# PowerManagement.net
KiCad netlist of a schematic drawn in Altium Designer
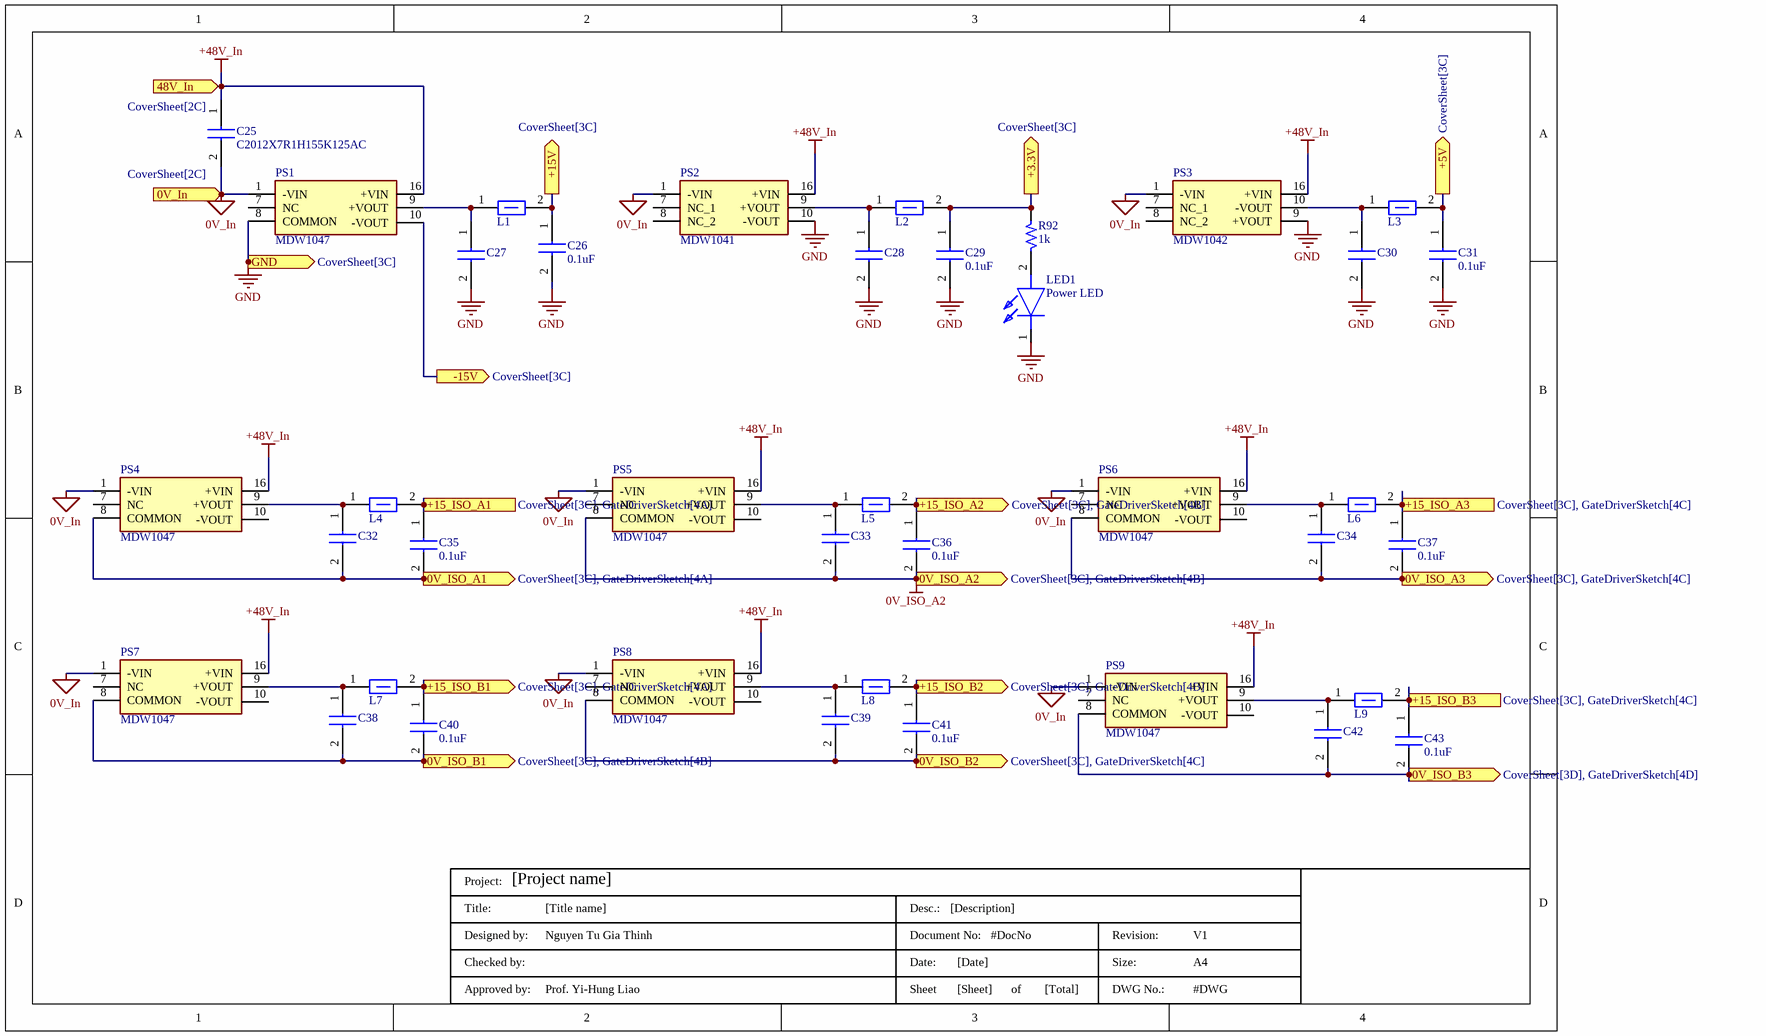
[diagram p0: PowerManagement.SchDoc]

(export (version "E")
  (design (tool "Eeschema 10.0.6"))
  (components
    (comp (ref "C25")
      (value "C2012X7R1H155K125AC")
      (footprint "SamacSys:CAPC2012X145N")
      (description "Capacitor")
      (fields (field (name "MOUSER PART NUMBER") "810-C2012X7R1H155K"))
      (libsource (lib "SamacSys") (part "C2012X7R1H155K125AC"))
    )
    (comp (ref "C26")
      (value "0.1uF")
      (footprint "SamacSys:C0805")
      (description "Capacitor")
      (fields
        (field (name "MANUFACTURER_PART_NUMBER") "C0805C104K3RACTU")
        (field (name "MOUSER PART NUMBER") "80-C0805C104K3R")
      )
      (libsource (lib "SamacSys") (part "C0805C104K3RACTU"))
    )
    (comp (ref "C27")
      (value "CGA4J1X7R1E335K125AC")
      (footprint "SamacSys:CAPC2012X145N")
      (description "Capacitor")
      (fields (field (name "MOUSER PART NUMBER") "810-CGA4J1X7R1E335K"))
      (libsource (lib "SamacSys") (part "CGA4J1X7R1E335K125AC"))
    )
    (comp (ref "C28")
      (value "CGA4J1X7R1E335K125AC")
      (footprint "SamacSys:CAPC2012X145N")
      (description "Capacitor")
      (fields (field (name "MOUSER PART NUMBER") "810-CGA4J1X7R1E335K"))
      (libsource (lib "SamacSys") (part "CGA4J1X7R1E335K125AC"))
    )
    (comp (ref "C29")
      (value "0.1uF")
      (footprint "SamacSys:C0805")
      (description "Capacitor")
      (fields
        (field (name "MANUFACTURER_PART_NUMBER") "C0805C104K3RACTU")
        (field (name "MOUSER PART NUMBER") "80-C0805C104K3R")
      )
      (libsource (lib "SamacSys") (part "C0805C104K3RACTU"))
    )
    (comp (ref "C30")
      (value "CGA4J1X7R1E335K125AC")
      (footprint "SamacSys:CAPC2012X145N")
      (description "Capacitor")
      (fields (field (name "MOUSER PART NUMBER") "810-CGA4J1X7R1E335K"))
      (libsource (lib "SamacSys") (part "CGA4J1X7R1E335K125AC"))
    )
    (comp (ref "C31")
      (value "0.1uF")
      (footprint "SamacSys:C0805")
      (description "Capacitor")
      (fields
        (field (name "MANUFACTURER_PART_NUMBER") "C0805C104K3RACTU")
        (field (name "MOUSER PART NUMBER") "80-C0805C104K3R")
      )
      (libsource (lib "SamacSys") (part "C0805C104K3RACTU"))
    )
    (comp (ref "C32")
      (value "CGA4J1X7R1E335K125AC")
      (footprint "SamacSys:CAPC2012X145N")
      (description "Capacitor")
      (fields (field (name "MOUSER PART NUMBER") "810-CGA4J1X7R1E335K"))
      (libsource (lib "SamacSys") (part "CGA4J1X7R1E335K125AC"))
    )
    (comp (ref "C33")
      (value "CGA4J1X7R1E335K125AC")
      (footprint "SamacSys:CAPC2012X145N")
      (description "Capacitor")
      (fields (field (name "MOUSER PART NUMBER") "810-CGA4J1X7R1E335K"))
      (libsource (lib "SamacSys") (part "CGA4J1X7R1E335K125AC"))
    )
    (comp (ref "C34")
      (value "CGA4J1X7R1E335K125AC")
      (footprint "SamacSys:CAPC2012X145N")
      (description "Capacitor")
      (fields (field (name "MOUSER PART NUMBER") "810-CGA4J1X7R1E335K"))
      (libsource (lib "SamacSys") (part "CGA4J1X7R1E335K125AC"))
    )
    (comp (ref "C35")
      (value "0.1uF")
      (footprint "SamacSys:C0805")
      (description "Capacitor")
      (fields
        (field (name "MANUFACTURER_PART_NUMBER") "C0805C104K3RACTU")
        (field (name "MOUSER PART NUMBER") "80-C0805C104K3R")
      )
      (libsource (lib "SamacSys") (part "C0805C104K3RACTU"))
    )
    (comp (ref "C36")
      (value "0.1uF")
      (footprint "SamacSys:C0805")
      (description "Capacitor")
      (fields
        (field (name "MANUFACTURER_PART_NUMBER") "C0805C104K3RACTU")
        (field (name "MOUSER PART NUMBER") "80-C0805C104K3R")
      )
      (libsource (lib "SamacSys") (part "C0805C104K3RACTU"))
    )
    (comp (ref "C37")
      (value "0.1uF")
      (footprint "SamacSys:C0805")
      (description "Capacitor")
      (fields
        (field (name "MANUFACTURER_PART_NUMBER") "C0805C104K3RACTU")
        (field (name "MOUSER PART NUMBER") "80-C0805C104K3R")
      )
      (libsource (lib "SamacSys") (part "C0805C104K3RACTU"))
    )
    (comp (ref "C38")
      (value "CGA4J1X7R1E335K125AC")
      (footprint "SamacSys:CAPC2012X145N")
      (description "Capacitor")
      (fields (field (name "MOUSER PART NUMBER") "810-CGA4J1X7R1E335K"))
      (libsource (lib "SamacSys") (part "CGA4J1X7R1E335K125AC"))
    )
    (comp (ref "C39")
      (value "CGA4J1X7R1E335K125AC")
      (footprint "SamacSys:CAPC2012X145N")
      (description "Capacitor")
      (fields (field (name "MOUSER PART NUMBER") "810-CGA4J1X7R1E335K"))
      (libsource (lib "SamacSys") (part "CGA4J1X7R1E335K125AC"))
    )
    (comp (ref "C40")
      (value "0.1uF")
      (footprint "SamacSys:C0805")
      (description "Capacitor")
      (fields
        (field (name "MANUFACTURER_PART_NUMBER") "C0805C104K3RACTU")
        (field (name "MOUSER PART NUMBER") "80-C0805C104K3R")
      )
      (libsource (lib "SamacSys") (part "C0805C104K3RACTU"))
    )
    (comp (ref "C41")
      (value "0.1uF")
      (footprint "SamacSys:C0805")
      (description "Capacitor")
      (fields
        (field (name "MANUFACTURER_PART_NUMBER") "C0805C104K3RACTU")
        (field (name "MOUSER PART NUMBER") "80-C0805C104K3R")
      )
      (libsource (lib "SamacSys") (part "C0805C104K3RACTU"))
    )
    (comp (ref "C42")
      (value "CGA4J1X7R1E335K125AC")
      (footprint "SamacSys:CAPC2012X145N")
      (description "Capacitor")
      (fields (field (name "MOUSER PART NUMBER") "810-CGA4J1X7R1E335K"))
      (libsource (lib "SamacSys") (part "CGA4J1X7R1E335K125AC"))
    )
    (comp (ref "C43")
      (value "0.1uF")
      (footprint "SamacSys:C0805")
      (description "Capacitor")
      (fields
        (field (name "MANUFACTURER_PART_NUMBER") "C0805C104K3RACTU")
        (field (name "MOUSER PART NUMBER") "80-C0805C104K3R")
      )
      (libsource (lib "SamacSys") (part "C0805C104K3RACTU"))
    )
    (comp (ref "L1")
      (value "MPZ2012S300A")
      (footprint "BEADC2012X105N")
      (description "Ferrite Bead")
      (fields (field (name "MOUSER PART NUMBER") "810-MPZ2012S300A"))
      (libsource (lib "ViennaRectifier") (part "MPZ2012S300A"))
    )
    (comp (ref "L2")
      (value "MPZ2012S300A")
      (footprint "BEADC2012X105N")
      (description "Ferrite Bead")
      (fields (field (name "MOUSER PART NUMBER") "810-MPZ2012S300A"))
      (libsource (lib "ViennaRectifier") (part "MPZ2012S300A"))
    )
    (comp (ref "L3")
      (value "MPZ2012S300A")
      (footprint "BEADC2012X105N")
      (description "Ferrite Bead")
      (fields (field (name "MOUSER PART NUMBER") "810-MPZ2012S300A"))
      (libsource (lib "ViennaRectifier") (part "MPZ2012S300A"))
    )
    (comp (ref "L4")
      (value "MPZ2012S300A")
      (footprint "BEADC2012X105N")
      (description "Ferrite Bead")
      (fields (field (name "MOUSER PART NUMBER") "810-MPZ2012S300A"))
      (libsource (lib "ViennaRectifier") (part "MPZ2012S300A"))
    )
    (comp (ref "L5")
      (value "MPZ2012S300A")
      (footprint "BEADC2012X105N")
      (description "Ferrite Bead")
      (fields (field (name "MOUSER PART NUMBER") "810-MPZ2012S300A"))
      (libsource (lib "ViennaRectifier") (part "MPZ2012S300A"))
    )
    (comp (ref "L6")
      (value "MPZ2012S300A")
      (footprint "BEADC2012X105N")
      (description "Ferrite Bead")
      (fields (field (name "MOUSER PART NUMBER") "810-MPZ2012S300A"))
      (libsource (lib "ViennaRectifier") (part "MPZ2012S300A"))
    )
    (comp (ref "L7")
      (value "MPZ2012S300A")
      (footprint "BEADC2012X105N")
      (description "Ferrite Bead")
      (fields (field (name "MOUSER PART NUMBER") "810-MPZ2012S300A"))
      (libsource (lib "ViennaRectifier") (part "MPZ2012S300A"))
    )
    (comp (ref "L8")
      (value "MPZ2012S300A")
      (footprint "BEADC2012X105N")
      (description "Ferrite Bead")
      (fields (field (name "MOUSER PART NUMBER") "810-MPZ2012S300A"))
      (libsource (lib "ViennaRectifier") (part "MPZ2012S300A"))
    )
    (comp (ref "L9")
      (value "MPZ2012S300A")
      (footprint "BEADC2012X105N")
      (description "Ferrite Bead")
      (fields (field (name "MOUSER PART NUMBER") "810-MPZ2012S300A"))
      (libsource (lib "ViennaRectifier") (part "MPZ2012S300A"))
    )
    (comp (ref "LED1")
      (value "Power LED")
      (footprint "SamacSys:LEDC2012X80N")
      (description "LED")
      (fields
        (field (name "MANUFACTURER_PART_NUMBER") "150080VS75000")
        (field (name "MOUSER PART NUMBER") "710-150080VS75000")
      )
      (libsource (lib "ViennaRectifier") (part "150080VS75000"))
    )
    (comp (ref "PS1")
      (value "MDW1047")
      (footprint "SamacSys:MDEU0205D12HI")
      (description "Power Supply")
      (libsource (lib "SamacSys") (part "MDW1047"))
    )
    (comp (ref "PS2")
      (value "MDW1041")
      (footprint "SamacSys:MDEU0205D12HI")
      (description "Power Supply")
      (libsource (lib "SamacSys") (part "MDW1041"))
    )
    (comp (ref "PS3")
      (value "MDW1042")
      (footprint "SamacSys:MDEU0205D12HI")
      (description "Power Supply")
      (libsource (lib "SamacSys") (part "MDW1042"))
    )
    (comp (ref "PS4")
      (value "MDW1047")
      (footprint "SamacSys:MDEU0205D12HI")
      (description "Power Supply")
      (libsource (lib "SamacSys") (part "MDW1047"))
    )
    (comp (ref "PS5")
      (value "MDW1047")
      (footprint "SamacSys:MDEU0205D12HI")
      (description "Power Supply")
      (libsource (lib "SamacSys") (part "MDW1047"))
    )
    (comp (ref "PS6")
      (value "MDW1047")
      (footprint "SamacSys:MDEU0205D12HI")
      (description "Power Supply")
      (libsource (lib "SamacSys") (part "MDW1047"))
    )
    (comp (ref "PS7")
      (value "MDW1047")
      (footprint "SamacSys:MDEU0205D12HI")
      (description "Power Supply")
      (libsource (lib "SamacSys") (part "MDW1047"))
    )
    (comp (ref "PS8")
      (value "MDW1047")
      (footprint "SamacSys:MDEU0205D12HI")
      (description "Power Supply")
      (libsource (lib "SamacSys") (part "MDW1047"))
    )
    (comp (ref "PS9")
      (value "MDW1047")
      (footprint "SamacSys:MDEU0205D12HI")
      (description "Power Supply")
      (libsource (lib "SamacSys") (part "MDW1047"))
    )
    (comp (ref "R92")
      (value "1k")
      (footprint "SM-1206")
      (description "Resistor 1/4W")
      (libsource (lib "ViennaRectifier") (part "R"))
    )
  )
  (nets
    (net (code "1") (name "+48V_In") (class "Default")
      (node (ref "C25") (pin "1") (pinfunction "1_1") (pintype "passive"))
      (node (ref "PS1") (pin "16") (pinfunction "+VIN_16") (pintype "passive"))
      (node (ref "PS2") (pin "16") (pinfunction "+VIN_16") (pintype "passive"))
      (node (ref "PS3") (pin "16") (pinfunction "+VIN_16") (pintype "passive"))
      (node (ref "PS4") (pin "16") (pinfunction "+VIN_16") (pintype "passive"))
      (node (ref "PS5") (pin "16") (pinfunction "+VIN_16") (pintype "passive"))
      (node (ref "PS6") (pin "16") (pinfunction "+VIN_16") (pintype "passive"))
      (node (ref "PS7") (pin "16") (pinfunction "+VIN_16") (pintype "passive"))
      (node (ref "PS8") (pin "16") (pinfunction "+VIN_16") (pintype "passive"))
      (node (ref "PS9") (pin "16") (pinfunction "+VIN_16") (pintype "passive"))
    )
    (net (code "2") (name "/+3.3V") (class "Default")
      (node (ref "C29") (pin "1") (pinfunction "1_1") (pintype "passive"))
      (node (ref "L2") (pin "2") (pinfunction "2_2") (pintype "passive"))
      (node (ref "R92") (pin "2") (pinfunction "2_2") (pintype "passive"))
    )
    (net (code "3") (name "/+5V") (class "Default")
      (node (ref "C31") (pin "1") (pinfunction "1_1") (pintype "passive"))
      (node (ref "L3") (pin "2") (pinfunction "2_2") (pintype "passive"))
    )
    (net (code "4") (name "/+15V") (class "Default")
      (node (ref "C26") (pin "1") (pinfunction "1_1") (pintype "passive"))
      (node (ref "L1") (pin "2") (pinfunction "2_2") (pintype "passive"))
    )
    (net (code "5") (name "/+15_ISO_A1") (class "Default")
      (node (ref "C35") (pin "1") (pinfunction "1_1") (pintype "passive"))
      (node (ref "L4") (pin "2") (pinfunction "2_2") (pintype "passive"))
    )
    (net (code "6") (name "/+15_ISO_A2") (class "Default")
      (node (ref "C36") (pin "1") (pinfunction "1_1") (pintype "passive"))
      (node (ref "L5") (pin "2") (pinfunction "2_2") (pintype "passive"))
    )
    (net (code "7") (name "/+15_ISO_A3") (class "Default")
      (node (ref "C37") (pin "1") (pinfunction "1_1") (pintype "passive"))
      (node (ref "L6") (pin "2") (pinfunction "2_2") (pintype "passive"))
    )
    (net (code "8") (name "/+15_ISO_B1") (class "Default")
      (node (ref "C40") (pin "1") (pinfunction "1_1") (pintype "passive"))
      (node (ref "L7") (pin "2") (pinfunction "2_2") (pintype "passive"))
    )
    (net (code "9") (name "/+15_ISO_B2") (class "Default")
      (node (ref "C41") (pin "1") (pinfunction "1_1") (pintype "passive"))
      (node (ref "L8") (pin "2") (pinfunction "2_2") (pintype "passive"))
    )
    (net (code "10") (name "/+15_ISO_B3") (class "Default")
      (node (ref "C43") (pin "1") (pinfunction "1_1") (pintype "passive"))
      (node (ref "L9") (pin "2") (pinfunction "2_2") (pintype "passive"))
    )
    (net (code "11") (name "/-15V") (class "Default")
      (node (ref "PS1") (pin "10") (pinfunction "-VOUT_10") (pintype "passive"))
    )
    (net (code "12") (name "/0V_ISO_A1") (class "Default")
      (node (ref "C32") (pin "2") (pinfunction "2_2") (pintype "passive"))
      (node (ref "C35") (pin "2") (pinfunction "2_2") (pintype "passive"))
      (node (ref "PS4") (pin "8") (pinfunction "COMMON_8") (pintype "passive"))
    )
    (net (code "13") (name "/0V_ISO_A3") (class "Default")
      (node (ref "C34") (pin "2") (pinfunction "2_2") (pintype "passive"))
      (node (ref "C37") (pin "2") (pinfunction "2_2") (pintype "passive"))
      (node (ref "PS6") (pin "8") (pinfunction "COMMON_8") (pintype "passive"))
    )
    (net (code "14") (name "/0V_ISO_B1") (class "Default")
      (node (ref "C38") (pin "2") (pinfunction "2_2") (pintype "passive"))
      (node (ref "C40") (pin "2") (pinfunction "2_2") (pintype "passive"))
      (node (ref "PS7") (pin "8") (pinfunction "COMMON_8") (pintype "passive"))
    )
    (net (code "15") (name "/0V_ISO_B2") (class "Default")
      (node (ref "C39") (pin "2") (pinfunction "2_2") (pintype "passive"))
      (node (ref "C41") (pin "2") (pinfunction "2_2") (pintype "passive"))
      (node (ref "PS8") (pin "8") (pinfunction "COMMON_8") (pintype "passive"))
    )
    (net (code "16") (name "/0V_ISO_B3") (class "Default")
      (node (ref "C42") (pin "2") (pinfunction "2_2") (pintype "passive"))
      (node (ref "C43") (pin "2") (pinfunction "2_2") (pintype "passive"))
      (node (ref "PS9") (pin "8") (pinfunction "COMMON_8") (pintype "passive"))
    )
    (net (code "17") (name "0V_ISO_A2") (class "Default")
      (node (ref "C33") (pin "2") (pinfunction "2_2") (pintype "passive"))
      (node (ref "C36") (pin "2") (pinfunction "2_2") (pintype "passive"))
      (node (ref "PS5") (pin "8") (pinfunction "COMMON_8") (pintype "passive"))
    )
    (net (code "18") (name "0V_In") (class "Default")
      (node (ref "C25") (pin "2") (pinfunction "2_2") (pintype "passive"))
      (node (ref "PS1") (pin "1") (pinfunction "-VIN_1") (pintype "passive"))
      (node (ref "PS2") (pin "1") (pinfunction "-VIN_1") (pintype "passive"))
      (node (ref "PS3") (pin "1") (pinfunction "-VIN_1") (pintype "passive"))
      (node (ref "PS4") (pin "1") (pinfunction "-VIN_1") (pintype "passive"))
      (node (ref "PS5") (pin "1") (pinfunction "-VIN_1") (pintype "passive"))
      (node (ref "PS6") (pin "1") (pinfunction "-VIN_1") (pintype "passive"))
      (node (ref "PS7") (pin "1") (pinfunction "-VIN_1") (pintype "passive"))
      (node (ref "PS8") (pin "1") (pinfunction "-VIN_1") (pintype "passive"))
      (node (ref "PS9") (pin "1") (pinfunction "-VIN_1") (pintype "passive"))
    )
    (net (code "19") (name "GND") (class "Default")
      (node (ref "C26") (pin "2") (pinfunction "2_2") (pintype "passive"))
      (node (ref "C27") (pin "2") (pinfunction "2_2") (pintype "passive"))
      (node (ref "C28") (pin "2") (pinfunction "2_2") (pintype "passive"))
      (node (ref "C29") (pin "2") (pinfunction "2_2") (pintype "passive"))
      (node (ref "C30") (pin "2") (pinfunction "2_2") (pintype "passive"))
      (node (ref "C31") (pin "2") (pinfunction "2_2") (pintype "passive"))
      (node (ref "LED1") (pin "1") (pinfunction "K_1") (pintype "passive"))
      (node (ref "PS1") (pin "8") (pinfunction "COMMON_8") (pintype "passive"))
      (node (ref "PS2") (pin "10") (pinfunction "-VOUT_10") (pintype "passive"))
      (node (ref "PS3") (pin "9") (pinfunction "+VOUT_9") (pintype "passive"))
    )
    (net (code "20") (name "Net-(LED1-A)") (class "Default")
      (node (ref "LED1") (pin "2") (pinfunction "A_2") (pintype "passive"))
      (node (ref "R92") (pin "1") (pinfunction "1_1") (pintype "passive"))
    )
    (net (code "21") (name "Net-(PS1-+VOUT)") (class "Default")
      (node (ref "C27") (pin "1") (pinfunction "1_1") (pintype "passive"))
      (node (ref "L1") (pin "1") (pinfunction "1_1") (pintype "passive"))
      (node (ref "PS1") (pin "9") (pinfunction "+VOUT_9") (pintype "passive"))
    )
    (net (code "22") (name "Net-(PS2-+VOUT)") (class "Default")
      (node (ref "C28") (pin "1") (pinfunction "1_1") (pintype "passive"))
      (node (ref "L2") (pin "1") (pinfunction "1_1") (pintype "passive"))
      (node (ref "PS2") (pin "9") (pinfunction "+VOUT_9") (pintype "passive"))
    )
    (net (code "23") (name "Net-(PS3--VOUT)") (class "Default")
      (node (ref "C30") (pin "1") (pinfunction "1_1") (pintype "passive"))
      (node (ref "L3") (pin "1") (pinfunction "1_1") (pintype "passive"))
      (node (ref "PS3") (pin "10") (pinfunction "-VOUT_10") (pintype "passive"))
    )
    (net (code "24") (name "Net-(PS4-+VOUT)") (class "Default")
      (node (ref "C32") (pin "1") (pinfunction "1_1") (pintype "passive"))
      (node (ref "L4") (pin "1") (pinfunction "1_1") (pintype "passive"))
      (node (ref "PS4") (pin "9") (pinfunction "+VOUT_9") (pintype "passive"))
    )
    (net (code "25") (name "Net-(PS5-+VOUT)") (class "Default")
      (node (ref "C33") (pin "1") (pinfunction "1_1") (pintype "passive"))
      (node (ref "L5") (pin "1") (pinfunction "1_1") (pintype "passive"))
      (node (ref "PS5") (pin "9") (pinfunction "+VOUT_9") (pintype "passive"))
    )
    (net (code "26") (name "Net-(PS6-+VOUT)") (class "Default")
      (node (ref "C34") (pin "1") (pinfunction "1_1") (pintype "passive"))
      (node (ref "L6") (pin "1") (pinfunction "1_1") (pintype "passive"))
      (node (ref "PS6") (pin "9") (pinfunction "+VOUT_9") (pintype "passive"))
    )
    (net (code "27") (name "Net-(PS7-+VOUT)") (class "Default")
      (node (ref "C38") (pin "1") (pinfunction "1_1") (pintype "passive"))
      (node (ref "L7") (pin "1") (pinfunction "1_1") (pintype "passive"))
      (node (ref "PS7") (pin "9") (pinfunction "+VOUT_9") (pintype "passive"))
    )
    (net (code "28") (name "Net-(PS8-+VOUT)") (class "Default")
      (node (ref "C39") (pin "1") (pinfunction "1_1") (pintype "passive"))
      (node (ref "L8") (pin "1") (pinfunction "1_1") (pintype "passive"))
      (node (ref "PS8") (pin "9") (pinfunction "+VOUT_9") (pintype "passive"))
    )
    (net (code "29") (name "Net-(PS9-+VOUT)") (class "Default")
      (node (ref "C42") (pin "1") (pinfunction "1_1") (pintype "passive"))
      (node (ref "L9") (pin "1") (pinfunction "1_1") (pintype "passive"))
      (node (ref "PS9") (pin "9") (pinfunction "+VOUT_9") (pintype "passive"))
    )
    (net (code "30") (name "unconnected-(PS1-NC-Pad7)") (class "Default")
      (node (ref "PS1") (pin "7") (pinfunction "NC_7") (pintype "passive"))
    )
    (net (code "31") (name "unconnected-(PS2-NC_1-Pad7)") (class "Default")
      (node (ref "PS2") (pin "7") (pinfunction "NC_1_7") (pintype "passive"))
    )
    (net (code "32") (name "unconnected-(PS2-NC_2-Pad8)") (class "Default")
      (node (ref "PS2") (pin "8") (pinfunction "NC_2_8") (pintype "passive"))
    )
    (net (code "33") (name "unconnected-(PS3-NC_1-Pad7)") (class "Default")
      (node (ref "PS3") (pin "7") (pinfunction "NC_1_7") (pintype "passive"))
    )
    (net (code "34") (name "unconnected-(PS3-NC_2-Pad8)") (class "Default")
      (node (ref "PS3") (pin "8") (pinfunction "NC_2_8") (pintype "passive"))
    )
    (net (code "35") (name "unconnected-(PS4--VOUT-Pad10)") (class "Default")
      (node (ref "PS4") (pin "10") (pinfunction "-VOUT_10") (pintype "passive"))
    )
    (net (code "36") (name "unconnected-(PS4-NC-Pad7)") (class "Default")
      (node (ref "PS4") (pin "7") (pinfunction "NC_7") (pintype "passive"))
    )
    (net (code "37") (name "unconnected-(PS5--VOUT-Pad10)") (class "Default")
      (node (ref "PS5") (pin "10") (pinfunction "-VOUT_10") (pintype "passive"))
    )
    (net (code "38") (name "unconnected-(PS5-NC-Pad7)") (class "Default")
      (node (ref "PS5") (pin "7") (pinfunction "NC_7") (pintype "passive"))
    )
    (net (code "39") (name "unconnected-(PS6--VOUT-Pad10)") (class "Default")
      (node (ref "PS6") (pin "10") (pinfunction "-VOUT_10") (pintype "passive"))
    )
    (net (code "40") (name "unconnected-(PS6-NC-Pad7)") (class "Default")
      (node (ref "PS6") (pin "7") (pinfunction "NC_7") (pintype "passive"))
    )
    (net (code "41") (name "unconnected-(PS7--VOUT-Pad10)") (class "Default")
      (node (ref "PS7") (pin "10") (pinfunction "-VOUT_10") (pintype "passive"))
    )
    (net (code "42") (name "unconnected-(PS7-NC-Pad7)") (class "Default")
      (node (ref "PS7") (pin "7") (pinfunction "NC_7") (pintype "passive"))
    )
    (net (code "43") (name "unconnected-(PS8--VOUT-Pad10)") (class "Default")
      (node (ref "PS8") (pin "10") (pinfunction "-VOUT_10") (pintype "passive"))
    )
    (net (code "44") (name "unconnected-(PS8-NC-Pad7)") (class "Default")
      (node (ref "PS8") (pin "7") (pinfunction "NC_7") (pintype "passive"))
    )
    (net (code "45") (name "unconnected-(PS9--VOUT-Pad10)") (class "Default")
      (node (ref "PS9") (pin "10") (pinfunction "-VOUT_10") (pintype "passive"))
    )
    (net (code "46") (name "unconnected-(PS9-NC-Pad7)") (class "Default")
      (node (ref "PS9") (pin "7") (pinfunction "NC_7") (pintype "passive"))
    )
  )
)
